# main_sheet.net
KiCad netlist of a schematic drawn in Altium Designer
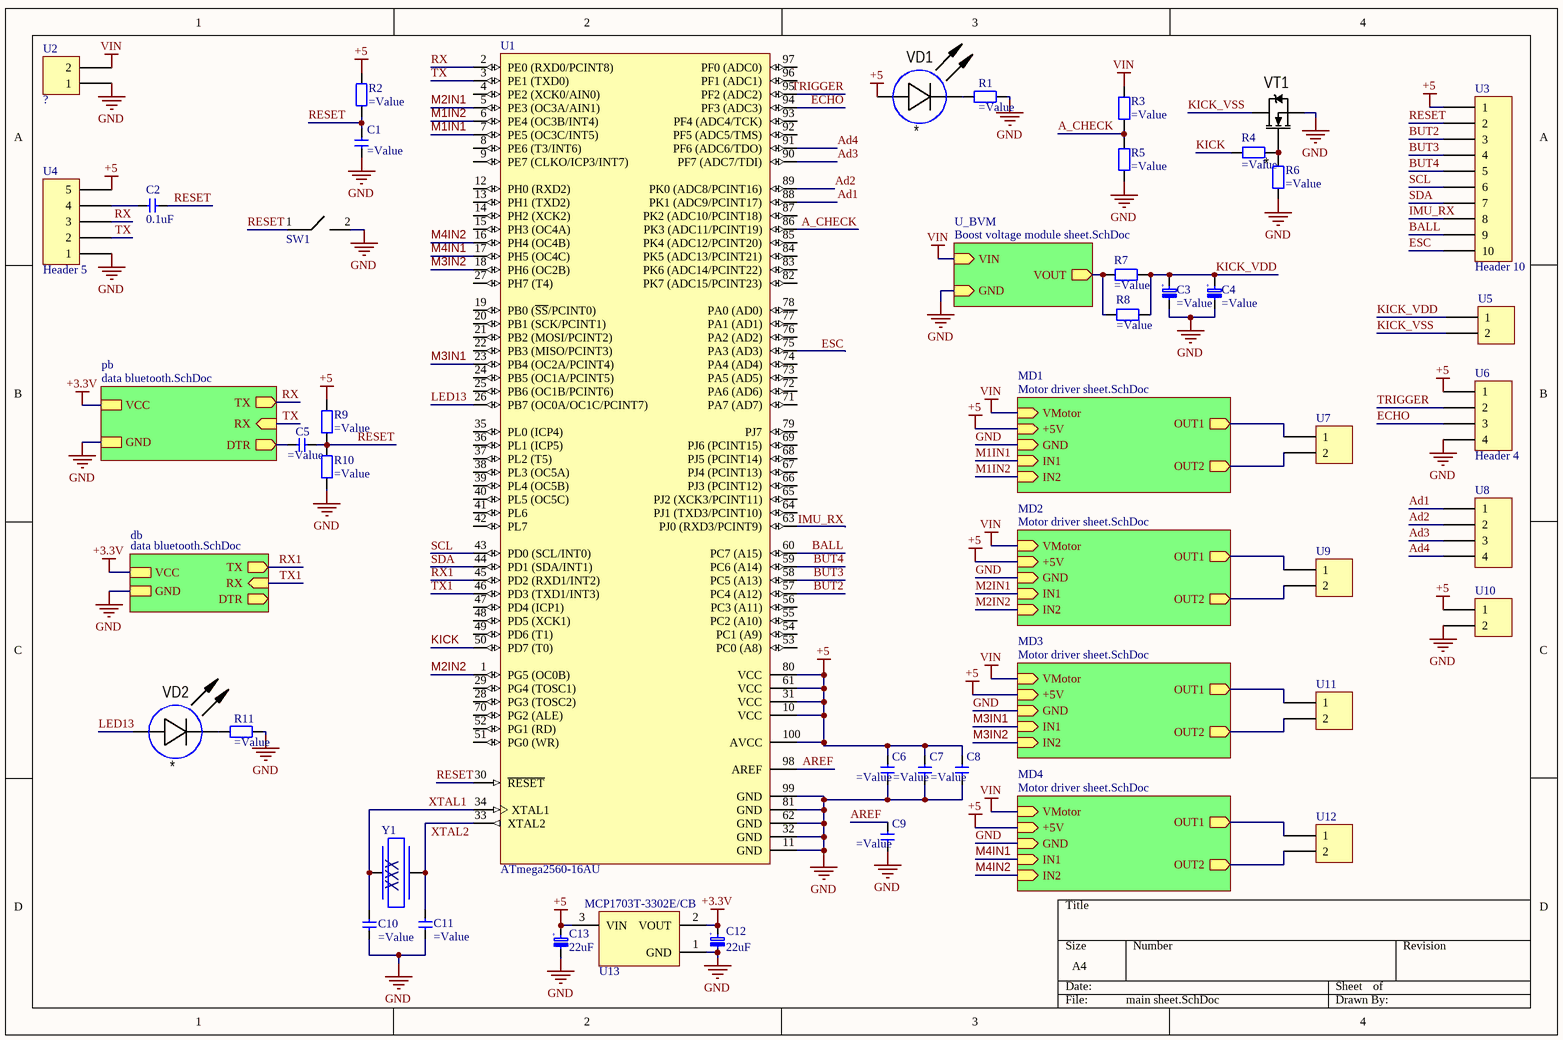
[diagram p0: main sheet.SchDoc]

(export (version "E")
  (design (tool "Eeschema 10.0.6"))
  (components
    (comp (ref "C1") (value "~") (footprint "cap0603") (libsource (lib "AlexChistiakov") (part "Cap SMD")))
    (comp (ref "C2")
      (value "0.1uF")
      (footprint "cap0603")
      (libsource (lib "AlexChistiakov") (part "Cap SMD"))
    )
    (comp (ref "C3")
      (value "~")
      (footprint "CAP63V2200uF")
      (libsource (lib "AlexChistiakov") (part "Cap Aluminum"))
    )
    (comp (ref "C4")
      (value "~")
      (footprint "CAP63V2200uF")
      (libsource (lib "AlexChistiakov") (part "Cap Aluminum"))
    )
    (comp (ref "C5") (value "~") (footprint "cap0603") (libsource (lib "AlexChistiakov") (part "Cap SMD")))
    (comp (ref "C6") (value "~") (footprint "cap0603") (libsource (lib "AlexChistiakov") (part "Cap SMD")))
    (comp (ref "C7") (value "~") (footprint "cap0603") (libsource (lib "AlexChistiakov") (part "Cap SMD")))
    (comp (ref "C8") (value "~") (footprint "cap0603") (libsource (lib "AlexChistiakov") (part "Cap SMD")))
    (comp (ref "C9") (value "~") (footprint "cap0603") (libsource (lib "AlexChistiakov") (part "Cap SMD")))
    (comp (ref "C10") (value "~") (footprint "cap0603") (libsource (lib "AlexChistiakov") (part "Cap SMD")))
    (comp (ref "C11") (value "~") (footprint "cap0603") (libsource (lib "AlexChistiakov") (part "Cap SMD")))
    (comp (ref "C12")
      (value "22uF")
      (footprint "Tantal B")
      (libsource (lib "Discrete smd") (part "Cap Tantal"))
    )
    (comp (ref "C13")
      (value "22uF")
      (footprint "Tantal B")
      (libsource (lib "Discrete smd") (part "Cap Tantal"))
    )
    (comp (ref "R1")
      (value "~")
      (footprint "res0603")
      (libsource (lib "AlexChistiakov") (part "Resistor SMD"))
    )
    (comp (ref "R2")
      (value "~")
      (footprint "res0603")
      (libsource (lib "AlexChistiakov") (part "Resistor SMD"))
    )
    (comp (ref "R3")
      (value "~")
      (footprint "res0603")
      (libsource (lib "AlexChistiakov") (part "Resistor SMD"))
    )
    (comp (ref "R4")
      (value "~")
      (footprint "res0603")
      (libsource (lib "AlexChistiakov") (part "Resistor SMD"))
    )
    (comp (ref "R5")
      (value "~")
      (footprint "res0603")
      (libsource (lib "AlexChistiakov") (part "Resistor SMD"))
    )
    (comp (ref "R6")
      (value "~")
      (footprint "res0603")
      (libsource (lib "AlexChistiakov") (part "Resistor SMD"))
    )
    (comp (ref "R7")
      (value "~")
      (footprint "smd2512")
      (libsource (lib "AlexChistiakov") (part "Resistor SMD"))
    )
    (comp (ref "R8")
      (value "~")
      (footprint "smd2512")
      (libsource (lib "AlexChistiakov") (part "Resistor SMD"))
    )
    (comp (ref "R9")
      (value "~")
      (footprint "res0603")
      (libsource (lib "AlexChistiakov") (part "Resistor SMD"))
    )
    (comp (ref "R10")
      (value "~")
      (footprint "res0603")
      (libsource (lib "AlexChistiakov") (part "Resistor SMD"))
    )
    (comp (ref "R11")
      (value "~")
      (footprint "res0603")
      (libsource (lib "AlexChistiakov") (part "Resistor SMD"))
    )
    (comp (ref "SW1")
      (value "Switch")
      (footprint "Switch")
      (libsource (lib "AlexChistiakov") (part "Switch"))
    )
    (comp (ref "U1")
      (value "ATmega2560-16AU")
      (footprint "100A_N")
      (fields (field (name "PUBLISHER") "Altium Limited"))
      (libsource (lib "Atmel Microcontroller 8-Bit megaAVR") (part "ATmega2560-16AU"))
    )
    (comp (ref "U2") (value "?") (footprint "XT30") (libsource (lib "") (part "Power connectors_1")))
    (comp (ref "U3")
      (value "Header 10")
      (footprint "10x1.25")
      (libsource (lib "AlexChistiakov") (part "Header 10"))
    )
    (comp (ref "U4")
      (value "Header 5")
      (footprint "5x2.54")
      (libsource (lib "AlexChistiakov") (part "Header 5"))
    )
    (comp (ref "U5")
      (value "?")
      (footprint "XT30")
      (libsource (lib "AlexChistiakov") (part "Power connectors"))
    )
    (comp (ref "U6")
      (value "Header 4")
      (footprint "4x1.27")
      (libsource (lib "AlexChistiakov") (part "Header 4"))
    )
    (comp (ref "U7")
      (value "Header 2")
      (footprint "2x2.54")
      (libsource (lib "AlexChistiakov") (part "Header 2"))
    )
    (comp (ref "U8")
      (value "Header 4")
      (footprint "4x1.25")
      (libsource (lib "AlexChistiakov") (part "Header 4"))
    )
    (comp (ref "U9")
      (value "Header 2")
      (footprint "2x2.54")
      (libsource (lib "AlexChistiakov") (part "Header 2"))
    )
    (comp (ref "U10") (value "Header 2") (footprint "2x1.25") (libsource (lib "") (part "Header 2_1")))
    (comp (ref "U11")
      (value "Header 2")
      (footprint "2x2.54")
      (libsource (lib "AlexChistiakov") (part "Header 2"))
    )
    (comp (ref "U12")
      (value "Header 2")
      (footprint "2x2.54")
      (libsource (lib "AlexChistiakov") (part "Header 2"))
    )
    (comp (ref "U13")
      (value "MCP1703T-3302E/CB")
      (footprint "SOT-23A-CB3_N")
      (fields (field (name "PUBLISHER") "Altium Limited"))
      (libsource (lib "Microchip Power Mgt Line Regulator") (part "MCP1703T-3302E/CB"))
    )
    (comp (ref "VD1") (value "*") (footprint "CH0603LB") (libsource (lib "Discrete") (part "LED")))
    (comp (ref "VD2") (value "*") (footprint "CH0603LB") (libsource (lib "Discrete") (part "LED")))
    (comp (ref "VT1")
      (value "*")
      (footprint "DPAK_132")
      (description "Mosfet")
      (libsource (lib "Transistor") (part "N-chanel"))
    )
    (comp (ref "Y1")
      (value "XXX")
      (footprint "QSMD3.2x2.5_A")
      (description "Кварцевый резонатор")
      (libsource (lib "TarabusLib_KOR") (part "Crystal"))
    )
  )
  (nets
    (net (code "1") (name "+3.3V") (class "Default")
      (node (ref "C12") (pin "2") (pinfunction "PLUS_2") (pintype "passive"))
      (node (ref "U13") (pin "2") (pinfunction "VOUT_2") (pintype "power_in"))
    )
    (net (code "2") (name "+5") (class "Default")
      (node (ref "C13") (pin "2") (pinfunction "PLUS_2") (pintype "passive"))
      (node (ref "C6") (pin "2") (pinfunction "2_2") (pintype "passive"))
      (node (ref "C7") (pin "2") (pinfunction "2_2") (pintype "passive"))
      (node (ref "C8") (pin "2") (pinfunction "2_2") (pintype "passive"))
      (node (ref "R2") (pin "2") (pinfunction "2_2") (pintype "passive"))
      (node (ref "R9") (pin "2") (pinfunction "2_2") (pintype "passive"))
      (node (ref "U1") (pin "10") (pinfunction "VCC_10") (pintype "power_in"))
      (node (ref "U1") (pin "100") (pinfunction "AVCC_100") (pintype "power_in"))
      (node (ref "U1") (pin "31") (pinfunction "VCC_31") (pintype "power_in"))
      (node (ref "U1") (pin "61") (pinfunction "VCC_61") (pintype "power_in"))
      (node (ref "U1") (pin "80") (pinfunction "VCC_80") (pintype "power_in"))
      (node (ref "U10") (pin "1") (pinfunction "1_1") (pintype "power_in"))
      (node (ref "U13") (pin "3") (pinfunction "VIN_3") (pintype "power_in"))
      (node (ref "U3") (pin "1") (pinfunction "1_1") (pintype "power_in"))
      (node (ref "U4") (pin "5") (pinfunction "5_5") (pintype "power_in"))
      (node (ref "U6") (pin "1") (pinfunction "1_1") (pintype "power_in"))
      (node (ref "VD1") (pin "1") (pinfunction "A_1") (pintype "passive"))
    )
    (net (code "3") (name "/AREF") (class "Default")
      (node (ref "C9") (pin "2") (pinfunction "2_2") (pintype "passive"))
      (node (ref "U1") (pin "98") (pinfunction "AREF_98") (pintype "power_in"))
    )
    (net (code "4") (name "/A_CHECK") (class "Default")
      (node (ref "R3") (pin "1") (pinfunction "1_1") (pintype "passive"))
      (node (ref "R5") (pin "2") (pinfunction "2_2") (pintype "passive"))
      (node (ref "U1") (pin "86") (pinfunction "PK3_(ADC11/PCINT19)_86") (pintype "bidirectional"))
    )
    (net (code "5") (name "/Ad1") (class "Default")
      (node (ref "U1") (pin "88") (pinfunction "PK1_(ADC9/PCINT17)_88") (pintype "bidirectional"))
      (node (ref "U8") (pin "1") (pinfunction "1_1") (pintype "power_in"))
    )
    (net (code "6") (name "/Ad2") (class "Default")
      (node (ref "U1") (pin "89") (pinfunction "PK0_(ADC8/PCINT16)_89") (pintype "bidirectional"))
      (node (ref "U8") (pin "2") (pinfunction "2_2") (pintype "power_in"))
    )
    (net (code "7") (name "/Ad3") (class "Default")
      (node (ref "U1") (pin "90") (pinfunction "PF7_(ADC7/TDI)_90") (pintype "bidirectional"))
      (node (ref "U8") (pin "3") (pinfunction "3_3") (pintype "power_in"))
    )
    (net (code "8") (name "/Ad4") (class "Default")
      (node (ref "U1") (pin "91") (pinfunction "PF6_(ADC6/TDO)_91") (pintype "bidirectional"))
      (node (ref "U8") (pin "4") (pinfunction "4_4") (pintype "power_in"))
    )
    (net (code "9") (name "/BALL") (class "Default")
      (node (ref "U1") (pin "60") (pinfunction "PC7_(A15)_60") (pintype "bidirectional"))
      (node (ref "U3") (pin "9") (pinfunction "9_9") (pintype "power_in"))
    )
    (net (code "10") (name "/BUT2") (class "Default")
      (node (ref "U1") (pin "57") (pinfunction "PC4_(A12)_57") (pintype "bidirectional"))
      (node (ref "U3") (pin "3") (pinfunction "3_3") (pintype "power_in"))
    )
    (net (code "11") (name "/BUT3") (class "Default")
      (node (ref "U1") (pin "58") (pinfunction "PC5_(A13)_58") (pintype "bidirectional"))
      (node (ref "U3") (pin "4") (pinfunction "4_4") (pintype "power_in"))
    )
    (net (code "12") (name "/BUT4") (class "Default")
      (node (ref "U1") (pin "59") (pinfunction "PC6_(A14)_59") (pintype "bidirectional"))
      (node (ref "U3") (pin "5") (pinfunction "5_5") (pintype "power_in"))
    )
    (net (code "13") (name "/DTR") (class "Default")
      (node (ref "C5") (pin "1") (pinfunction "1_1") (pintype "passive"))
    )
    (net (code "15") (name "/ECHO") (class "Default")
      (node (ref "U1") (pin "94") (pinfunction "PF3_(ADC3)_94") (pintype "bidirectional"))
      (node (ref "U6") (pin "3") (pinfunction "3_3") (pintype "power_in"))
    )
    (net (code "16") (name "/ESC") (class "Default")
      (node (ref "U1") (pin "75") (pinfunction "PA3_(AD3)_75") (pintype "bidirectional"))
      (node (ref "U3") (pin "10") (pinfunction "10_10") (pintype "power_in"))
    )
    (net (code "17") (name "/IMU_RX") (class "Default")
      (node (ref "U1") (pin "63") (pinfunction "PJ0_(RXD3/PCINT9)_63") (pintype "bidirectional"))
      (node (ref "U3") (pin "8") (pinfunction "8_8") (pintype "power_in"))
    )
    (net (code "18") (name "/KICK") (class "Default")
      (node (ref "R4") (pin "1") (pinfunction "1_1") (pintype "passive"))
      (node (ref "U1") (pin "50") (pinfunction "PD7_(T0)_50") (pintype "bidirectional"))
    )
    (net (code "19") (name "/KICK_VDD") (class "Default")
      (node (ref "C3") (pin "1") (pinfunction "PLUS_1") (pintype "passive"))
      (node (ref "C4") (pin "1") (pinfunction "PLUS_1") (pintype "passive"))
      (node (ref "R7") (pin "2") (pinfunction "2_2") (pintype "passive"))
      (node (ref "R8") (pin "2") (pinfunction "2_2") (pintype "passive"))
      (node (ref "U5") (pin "1") (pinfunction "1_1") (pintype "power_in"))
    )
    (net (code "20") (name "/KICK_VSS") (class "Default")
      (node (ref "U5") (pin "2") (pinfunction "2_2") (pintype "power_in"))
      (node (ref "VT1") (pin "2") (pinfunction "D_2") (pintype "passive"))
    )
    (net (code "21") (name "/LED13") (class "Default")
      (node (ref "U1") (pin "26") (pinfunction "PB7_(OC0A/OC1C/PCINT7)_26") (pintype "bidirectional"))
      (node (ref "VD2") (pin "1") (pinfunction "A_1") (pintype "passive"))
    )
    (net (code "22") (name "/M1IN1") (class "Default")
      (node (ref "U1") (pin "7") (pinfunction "PE5_(OC3C/INT5)_7") (pintype "bidirectional"))
    )
    (net (code "23") (name "/M1IN2") (class "Default")
      (node (ref "U1") (pin "6") (pinfunction "PE4_(OC3B/INT4)_6") (pintype "bidirectional"))
    )
    (net (code "24") (name "/M2IN1") (class "Default")
      (node (ref "U1") (pin "5") (pinfunction "PE3_(OC3A/AIN1)_5") (pintype "bidirectional"))
    )
    (net (code "25") (name "/M2IN2") (class "Default")
      (node (ref "U1") (pin "1") (pinfunction "PG5_(OC0B)_1") (pintype "bidirectional"))
    )
    (net (code "26") (name "/M3IN1") (class "Default")
      (node (ref "U1") (pin "23") (pinfunction "PB4_(OC2A/PCINT4)_23") (pintype "bidirectional"))
    )
    (net (code "27") (name "/M3IN2") (class "Default")
      (node (ref "U1") (pin "18") (pinfunction "PH6_(OC2B)_18") (pintype "bidirectional"))
    )
    (net (code "28") (name "/M4IN1") (class "Default")
      (node (ref "U1") (pin "17") (pinfunction "PH5_(OC4C)_17") (pintype "bidirectional"))
    )
    (net (code "29") (name "/M4IN2") (class "Default")
      (node (ref "U1") (pin "16") (pinfunction "PH4_(OC4B)_16") (pintype "bidirectional"))
    )
    (net (code "30") (name "/OUT1") (class "Default")
      (node (ref "U11") (pin "1") (pinfunction "1_1") (pintype "power_in"))
    )
    (net (code "31") (name "/OUT1_1") (class "Default")
      (node (ref "U9") (pin "1") (pinfunction "1_1") (pintype "power_in"))
    )
    (net (code "32") (name "/OUT1_2") (class "Default")
      (node (ref "U7") (pin "1") (pinfunction "1_1") (pintype "power_in"))
    )
    (net (code "33") (name "/OUT1_3") (class "Default")
      (node (ref "U12") (pin "1") (pinfunction "1_1") (pintype "power_in"))
    )
    (net (code "34") (name "/OUT2") (class "Default")
      (node (ref "U11") (pin "2") (pinfunction "2_2") (pintype "power_in"))
    )
    (net (code "35") (name "/OUT2_1") (class "Default")
      (node (ref "U9") (pin "2") (pinfunction "2_2") (pintype "power_in"))
    )
    (net (code "36") (name "/OUT2_2") (class "Default")
      (node (ref "U7") (pin "2") (pinfunction "2_2") (pintype "power_in"))
    )
    (net (code "37") (name "/OUT2_3") (class "Default")
      (node (ref "U12") (pin "2") (pinfunction "2_2") (pintype "power_in"))
    )
    (net (code "38") (name "/RESET") (class "Default")
      (node (ref "C1") (pin "2") (pinfunction "2_2") (pintype "passive"))
      (node (ref "C2") (pin "2") (pinfunction "2_2") (pintype "passive"))
      (node (ref "C5") (pin "2") (pinfunction "2_2") (pintype "passive"))
      (node (ref "R10") (pin "2") (pinfunction "2_2") (pintype "passive"))
      (node (ref "R2") (pin "1") (pinfunction "1_1") (pintype "passive"))
      (node (ref "R9") (pin "1") (pinfunction "1_1") (pintype "passive"))
      (node (ref "SW1") (pin "1") (pinfunction "1_1") (pintype "passive"))
      (node (ref "U1") (pin "30") (pinfunction "~{RESET}_30") (pintype "input"))
      (node (ref "U3") (pin "2") (pinfunction "2_2") (pintype "power_in"))
    )
    (net (code "39") (name "/RX") (class "Default")
      (node (ref "U1") (pin "2") (pinfunction "PE0_(RXD0/PCINT8)_2") (pintype "bidirectional"))
      (node (ref "U4") (pin "3") (pinfunction "3_3") (pintype "power_in"))
    )
    (net (code "40") (name "/RX1") (class "Default")
      (node (ref "U1") (pin "45") (pinfunction "PD2_(RXD1/INT2)_45") (pintype "bidirectional"))
    )
    (net (code "41") (name "/SCL") (class "Default")
      (node (ref "U1") (pin "43") (pinfunction "PD0_(SCL/INT0)_43") (pintype "bidirectional"))
      (node (ref "U3") (pin "6") (pinfunction "6_6") (pintype "power_in"))
    )
    (net (code "42") (name "/SDA") (class "Default")
      (node (ref "U1") (pin "44") (pinfunction "PD1_(SDA/INT1)_44") (pintype "bidirectional"))
      (node (ref "U3") (pin "7") (pinfunction "7_7") (pintype "power_in"))
    )
    (net (code "43") (name "/TRIGGER") (class "Default")
      (node (ref "U1") (pin "95") (pinfunction "PF2_(ADC2)_95") (pintype "bidirectional"))
      (node (ref "U6") (pin "2") (pinfunction "2_2") (pintype "power_in"))
    )
    (net (code "44") (name "/TX") (class "Default")
      (node (ref "U1") (pin "3") (pinfunction "PE1_(TXD0)_3") (pintype "bidirectional"))
      (node (ref "U4") (pin "2") (pinfunction "2_2") (pintype "power_in"))
    )
    (net (code "45") (name "/TX1") (class "Default")
      (node (ref "U1") (pin "46") (pinfunction "PD3_(TXD1/INT3)_46") (pintype "bidirectional"))
    )
    (net (code "46") (name "/VOUT") (class "Default")
      (node (ref "R7") (pin "1") (pinfunction "1_1") (pintype "passive"))
      (node (ref "R8") (pin "1") (pinfunction "1_1") (pintype "passive"))
    )
    (net (code "47") (name "/XTAL1") (class "Default")
      (node (ref "C10") (pin "2") (pinfunction "2_2") (pintype "passive"))
      (node (ref "U1") (pin "34") (pinfunction "XTAL1_34") (pintype "input"))
      (node (ref "Y1") (pin "1") (pinfunction "1_1") (pintype "passive"))
    )
    (net (code "48") (name "/XTAL2") (class "Default")
      (node (ref "C11") (pin "2") (pinfunction "2_2") (pintype "passive"))
      (node (ref "U1") (pin "33") (pinfunction "XTAL2_33") (pintype "output"))
      (node (ref "Y1") (pin "2") (pinfunction "2_2") (pintype "passive"))
    )
    (net (code "49") (name "GND") (class "Default")
      (node (ref "C1") (pin "1") (pinfunction "1_1") (pintype "passive"))
      (node (ref "C10") (pin "1") (pinfunction "1_1") (pintype "passive"))
      (node (ref "C11") (pin "1") (pinfunction "1_1") (pintype "passive"))
      (node (ref "C12") (pin "1") (pinfunction "MINUS_1") (pintype "passive"))
      (node (ref "C13") (pin "1") (pinfunction "MINUS_1") (pintype "passive"))
      (node (ref "C3") (pin "2") (pinfunction "MINUS_2") (pintype "passive"))
      (node (ref "C4") (pin "2") (pinfunction "MINUS_2") (pintype "passive"))
      (node (ref "C6") (pin "1") (pinfunction "1_1") (pintype "passive"))
      (node (ref "C7") (pin "1") (pinfunction "1_1") (pintype "passive"))
      (node (ref "C8") (pin "1") (pinfunction "1_1") (pintype "passive"))
      (node (ref "C9") (pin "1") (pinfunction "1_1") (pintype "passive"))
      (node (ref "R1") (pin "2") (pinfunction "2_2") (pintype "passive"))
      (node (ref "R10") (pin "1") (pinfunction "1_1") (pintype "passive"))
      (node (ref "R11") (pin "2") (pinfunction "2_2") (pintype "passive"))
      (node (ref "R5") (pin "1") (pinfunction "1_1") (pintype "passive"))
      (node (ref "R6") (pin "1") (pinfunction "1_1") (pintype "passive"))
      (node (ref "SW1") (pin "2") (pinfunction "2_2") (pintype "passive"))
      (node (ref "U1") (pin "11") (pinfunction "GND_11") (pintype "power_in"))
      (node (ref "U1") (pin "32") (pinfunction "GND_32") (pintype "power_in"))
      (node (ref "U1") (pin "62") (pinfunction "GND_62") (pintype "power_in"))
      (node (ref "U1") (pin "81") (pinfunction "GND_81") (pintype "power_in"))
      (node (ref "U1") (pin "99") (pinfunction "GND_99") (pintype "power_in"))
      (node (ref "U10") (pin "2") (pinfunction "2_2") (pintype "power_in"))
      (node (ref "U13") (pin "1") (pinfunction "GND_1") (pintype "power_in"))
      (node (ref "U2") (pin "1") (pinfunction "1_1") (pintype "power_in"))
      (node (ref "U4") (pin "1") (pinfunction "1_1") (pintype "power_in"))
      (node (ref "U6") (pin "4") (pinfunction "4_4") (pintype "power_in"))
      (node (ref "VT1") (pin "3") (pinfunction "S_3") (pintype "passive"))
    )
    (net (code "50") (name "Net-(C2-Pad1)") (class "Default")
      (node (ref "C2") (pin "1") (pinfunction "1_1") (pintype "passive"))
      (node (ref "U4") (pin "4") (pinfunction "4_4") (pintype "power_in"))
    )
    (net (code "51") (name "Net-(VD1-C)") (class "Default")
      (node (ref "R1") (pin "1") (pinfunction "1_1") (pintype "passive"))
      (node (ref "VD1") (pin "2") (pinfunction "C_2") (pintype "passive"))
    )
    (net (code "52") (name "Net-(VD2-C)") (class "Default")
      (node (ref "R11") (pin "1") (pinfunction "1_1") (pintype "passive"))
      (node (ref "VD2") (pin "2") (pinfunction "C_2") (pintype "passive"))
    )
    (net (code "53") (name "Net-(VT1-G)") (class "Default")
      (node (ref "R4") (pin "2") (pinfunction "2_2") (pintype "passive"))
      (node (ref "R6") (pin "2") (pinfunction "2_2") (pintype "passive"))
      (node (ref "VT1") (pin "1") (pinfunction "G_1") (pintype "passive"))
    )
    (net (code "54") (name "VIN") (class "Default")
      (node (ref "R3") (pin "2") (pinfunction "2_2") (pintype "passive"))
      (node (ref "U2") (pin "2") (pinfunction "2_2") (pintype "power_in"))
    )
    (net (code "55") (name "unconnected-(U1-PA0_(AD0)-Pad78)") (class "Default")
      (node (ref "U1") (pin "78") (pinfunction "PA0_(AD0)_78") (pintype "bidirectional"))
    )
    (net (code "56") (name "unconnected-(U1-PA1_(AD1)-Pad77)") (class "Default")
      (node (ref "U1") (pin "77") (pinfunction "PA1_(AD1)_77") (pintype "bidirectional"))
    )
    (net (code "57") (name "unconnected-(U1-PA2_(AD2)-Pad76)") (class "Default")
      (node (ref "U1") (pin "76") (pinfunction "PA2_(AD2)_76") (pintype "bidirectional"))
    )
    (net (code "58") (name "unconnected-(U1-PA4_(AD4)-Pad74)") (class "Default")
      (node (ref "U1") (pin "74") (pinfunction "PA4_(AD4)_74") (pintype "bidirectional"))
    )
    (net (code "59") (name "unconnected-(U1-PA5_(AD5)-Pad73)") (class "Default")
      (node (ref "U1") (pin "73") (pinfunction "PA5_(AD5)_73") (pintype "bidirectional"))
    )
    (net (code "60") (name "unconnected-(U1-PA6_(AD6)-Pad72)") (class "Default")
      (node (ref "U1") (pin "72") (pinfunction "PA6_(AD6)_72") (pintype "bidirectional"))
    )
    (net (code "61") (name "unconnected-(U1-PA7_(AD7)-Pad71)") (class "Default")
      (node (ref "U1") (pin "71") (pinfunction "PA7_(AD7)_71") (pintype "bidirectional"))
    )
    (net (code "62") (name "unconnected-(U1-PB0_(~{SS}{slash}PCINT0)-Pad19)") (class "Default")
      (node (ref "U1") (pin "19") (pinfunction "PB0_(~{SS}/PCINT0)_19") (pintype "bidirectional"))
    )
    (net (code "63") (name "unconnected-(U1-PB1_(SCK{slash}PCINT1)-Pad20)") (class "Default")
      (node (ref "U1") (pin "20") (pinfunction "PB1_(SCK/PCINT1)_20") (pintype "bidirectional"))
    )
    (net (code "64") (name "unconnected-(U1-PB2_(MOSI{slash}PCINT2)-Pad21)") (class "Default")
      (node (ref "U1") (pin "21") (pinfunction "PB2_(MOSI/PCINT2)_21") (pintype "bidirectional"))
    )
    (net (code "65") (name "unconnected-(U1-PB3_(MISO{slash}PCINT3)-Pad22)") (class "Default")
      (node (ref "U1") (pin "22") (pinfunction "PB3_(MISO/PCINT3)_22") (pintype "bidirectional"))
    )
    (net (code "66") (name "unconnected-(U1-PB5_(OC1A{slash}PCINT5)-Pad24)") (class "Default")
      (node (ref "U1") (pin "24") (pinfunction "PB5_(OC1A/PCINT5)_24") (pintype "bidirectional"))
    )
    (net (code "67") (name "unconnected-(U1-PB6_(OC1B{slash}PCINT6)-Pad25)") (class "Default")
      (node (ref "U1") (pin "25") (pinfunction "PB6_(OC1B/PCINT6)_25") (pintype "bidirectional"))
    )
    (net (code "68") (name "unconnected-(U1-PC0_(A8)-Pad53)") (class "Default")
      (node (ref "U1") (pin "53") (pinfunction "PC0_(A8)_53") (pintype "bidirectional"))
    )
    (net (code "69") (name "unconnected-(U1-PC1_(A9)-Pad54)") (class "Default")
      (node (ref "U1") (pin "54") (pinfunction "PC1_(A9)_54") (pintype "bidirectional"))
    )
    (net (code "70") (name "unconnected-(U1-PC2_(A10)-Pad55)") (class "Default")
      (node (ref "U1") (pin "55") (pinfunction "PC2_(A10)_55") (pintype "bidirectional"))
    )
    (net (code "71") (name "unconnected-(U1-PC3_(A11)-Pad56)") (class "Default")
      (node (ref "U1") (pin "56") (pinfunction "PC3_(A11)_56") (pintype "bidirectional"))
    )
    (net (code "72") (name "unconnected-(U1-PD4_(ICP1)-Pad47)") (class "Default")
      (node (ref "U1") (pin "47") (pinfunction "PD4_(ICP1)_47") (pintype "bidirectional"))
    )
    (net (code "73") (name "unconnected-(U1-PD5_(XCK1)-Pad48)") (class "Default")
      (node (ref "U1") (pin "48") (pinfunction "PD5_(XCK1)_48") (pintype "bidirectional"))
    )
    (net (code "74") (name "unconnected-(U1-PD6_(T1)-Pad49)") (class "Default")
      (node (ref "U1") (pin "49") (pinfunction "PD6_(T1)_49") (pintype "bidirectional"))
    )
    (net (code "75") (name "unconnected-(U1-PE2_(XCK0{slash}AIN0)-Pad4)") (class "Default")
      (node (ref "U1") (pin "4") (pinfunction "PE2_(XCK0/AIN0)_4") (pintype "bidirectional"))
    )
    (net (code "76") (name "unconnected-(U1-PE6_(T3{slash}INT6)-Pad8)") (class "Default")
      (node (ref "U1") (pin "8") (pinfunction "PE6_(T3/INT6)_8") (pintype "bidirectional"))
    )
    (net (code "77") (name "unconnected-(U1-PE7_(CLKO{slash}ICP3{slash}INT7)-Pad9)") (class "Default")
      (node (ref "U1") (pin "9") (pinfunction "PE7_(CLKO/ICP3/INT7)_9") (pintype "bidirectional"))
    )
    (net (code "78") (name "unconnected-(U1-PF0_(ADC0)-Pad97)") (class "Default")
      (node (ref "U1") (pin "97") (pinfunction "PF0_(ADC0)_97") (pintype "bidirectional"))
    )
    (net (code "79") (name "unconnected-(U1-PF1_(ADC1)-Pad96)") (class "Default")
      (node (ref "U1") (pin "96") (pinfunction "PF1_(ADC1)_96") (pintype "bidirectional"))
    )
    (net (code "80") (name "unconnected-(U1-PF4_(ADC4{slash}TCK)-Pad93)") (class "Default")
      (node (ref "U1") (pin "93") (pinfunction "PF4_(ADC4/TCK)_93") (pintype "bidirectional"))
    )
    (net (code "81") (name "unconnected-(U1-PF5_(ADC5{slash}TMS)-Pad92)") (class "Default")
      (node (ref "U1") (pin "92") (pinfunction "PF5_(ADC5/TMS)_92") (pintype "bidirectional"))
    )
    (net (code "82") (name "unconnected-(U1-PG0_(WR)-Pad51)") (class "Default")
      (node (ref "U1") (pin "51") (pinfunction "PG0_(WR)_51") (pintype "bidirectional"))
    )
    (net (code "83") (name "unconnected-(U1-PG1_(RD)-Pad52)") (class "Default")
      (node (ref "U1") (pin "52") (pinfunction "PG1_(RD)_52") (pintype "bidirectional"))
    )
    (net (code "84") (name "unconnected-(U1-PG2_(ALE)-Pad70)") (class "Default")
      (node (ref "U1") (pin "70") (pinfunction "PG2_(ALE)_70") (pintype "bidirectional"))
    )
    (net (code "85") (name "unconnected-(U1-PG3_(TOSC2)-Pad28)") (class "Default")
      (node (ref "U1") (pin "28") (pinfunction "PG3_(TOSC2)_28") (pintype "bidirectional"))
    )
    (net (code "86") (name "unconnected-(U1-PG4_(TOSC1)-Pad29)") (class "Default")
      (node (ref "U1") (pin "29") (pinfunction "PG4_(TOSC1)_29") (pintype "bidirectional"))
    )
    (net (code "87") (name "unconnected-(U1-PH0_(RXD2)-Pad12)") (class "Default")
      (node (ref "U1") (pin "12") (pinfunction "PH0_(RXD2)_12") (pintype "bidirectional"))
    )
    (net (code "88") (name "unconnected-(U1-PH1_(TXD2)-Pad13)") (class "Default")
      (node (ref "U1") (pin "13") (pinfunction "PH1_(TXD2)_13") (pintype "bidirectional"))
    )
    (net (code "89") (name "unconnected-(U1-PH2_(XCK2)-Pad14)") (class "Default")
      (node (ref "U1") (pin "14") (pinfunction "PH2_(XCK2)_14") (pintype "bidirectional"))
    )
    (net (code "90") (name "unconnected-(U1-PH3_(OC4A)-Pad15)") (class "Default")
      (node (ref "U1") (pin "15") (pinfunction "PH3_(OC4A)_15") (pintype "bidirectional"))
    )
    (net (code "91") (name "unconnected-(U1-PH7_(T4)-Pad27)") (class "Default")
      (node (ref "U1") (pin "27") (pinfunction "PH7_(T4)_27") (pintype "bidirectional"))
    )
    (net (code "92") (name "unconnected-(U1-PJ1_(TXD3{slash}PCINT10)-Pad64)") (class "Default")
      (node (ref "U1") (pin "64") (pinfunction "PJ1_(TXD3/PCINT10)_64") (pintype "bidirectional"))
    )
    (net (code "93") (name "unconnected-(U1-PJ2_(XCK3{slash}PCINT11)-Pad65)") (class "Default")
      (node (ref "U1") (pin "65") (pinfunction "PJ2_(XCK3/PCINT11)_65") (pintype "bidirectional"))
    )
    (net (code "94") (name "unconnected-(U1-PJ3_(PCINT12)-Pad66)") (class "Default")
      (node (ref "U1") (pin "66") (pinfunction "PJ3_(PCINT12)_66") (pintype "bidirectional"))
    )
    (net (code "95") (name "unconnected-(U1-PJ4_(PCINT13)-Pad67)") (class "Default")
      (node (ref "U1") (pin "67") (pinfunction "PJ4_(PCINT13)_67") (pintype "bidirectional"))
    )
    (net (code "96") (name "unconnected-(U1-PJ5_(PCINT14)-Pad68)") (class "Default")
      (node (ref "U1") (pin "68") (pinfunction "PJ5_(PCINT14)_68") (pintype "bidirectional"))
    )
    (net (code "97") (name "unconnected-(U1-PJ6_(PCINT15)-Pad69)") (class "Default")
      (node (ref "U1") (pin "69") (pinfunction "PJ6_(PCINT15)_69") (pintype "bidirectional"))
    )
    (net (code "98") (name "unconnected-(U1-PJ7-Pad79)") (class "Default")
      (node (ref "U1") (pin "79") (pinfunction "PJ7_79") (pintype "bidirectional"))
    )
    (net (code "99") (name "unconnected-(U1-PK2_(ADC10{slash}PCINT18)-Pad87)") (class "Default")
      (node (ref "U1") (pin "87") (pinfunction "PK2_(ADC10/PCINT18)_87") (pintype "bidirectional"))
    )
    (net (code "100") (name "unconnected-(U1-PK4_(ADC12{slash}PCINT20)-Pad85)") (class "Default")
      (node (ref "U1") (pin "85") (pinfunction "PK4_(ADC12/PCINT20)_85") (pintype "bidirectional"))
    )
    (net (code "101") (name "unconnected-(U1-PK5_(ADC13{slash}PCINT21)-Pad84)") (class "Default")
      (node (ref "U1") (pin "84") (pinfunction "PK5_(ADC13/PCINT21)_84") (pintype "bidirectional"))
    )
    (net (code "102") (name "unconnected-(U1-PK6_(ADC14{slash}PCINT22)-Pad83)") (class "Default")
      (node (ref "U1") (pin "83") (pinfunction "PK6_(ADC14/PCINT22)_83") (pintype "bidirectional"))
    )
    (net (code "103") (name "unconnected-(U1-PK7_(ADC15{slash}PCINT23)-Pad82)") (class "Default")
      (node (ref "U1") (pin "82") (pinfunction "PK7_(ADC15/PCINT23)_82") (pintype "bidirectional"))
    )
    (net (code "104") (name "unconnected-(U1-PL0_(ICP4)-Pad35)") (class "Default")
      (node (ref "U1") (pin "35") (pinfunction "PL0_(ICP4)_35") (pintype "bidirectional"))
    )
    (net (code "105") (name "unconnected-(U1-PL1_(ICP5)-Pad36)") (class "Default")
      (node (ref "U1") (pin "36") (pinfunction "PL1_(ICP5)_36") (pintype "bidirectional"))
    )
    (net (code "106") (name "unconnected-(U1-PL2_(T5)-Pad37)") (class "Default")
      (node (ref "U1") (pin "37") (pinfunction "PL2_(T5)_37") (pintype "bidirectional"))
    )
    (net (code "107") (name "unconnected-(U1-PL3_(OC5A)-Pad38)") (class "Default")
      (node (ref "U1") (pin "38") (pinfunction "PL3_(OC5A)_38") (pintype "bidirectional"))
    )
    (net (code "108") (name "unconnected-(U1-PL4_(OC5B)-Pad39)") (class "Default")
      (node (ref "U1") (pin "39") (pinfunction "PL4_(OC5B)_39") (pintype "bidirectional"))
    )
    (net (code "109") (name "unconnected-(U1-PL5_(OC5C)-Pad40)") (class "Default")
      (node (ref "U1") (pin "40") (pinfunction "PL5_(OC5C)_40") (pintype "bidirectional"))
    )
    (net (code "110") (name "unconnected-(U1-PL6-Pad41)") (class "Default")
      (node (ref "U1") (pin "41") (pinfunction "PL6_41") (pintype "bidirectional"))
    )
    (net (code "111") (name "unconnected-(U1-PL7-Pad42)") (class "Default")
      (node (ref "U1") (pin "42") (pinfunction "PL7_42") (pintype "bidirectional"))
    )
  )
)
